# X-A4U-RGB.net
KiCad netlist of a schematic drawn in EAGLE
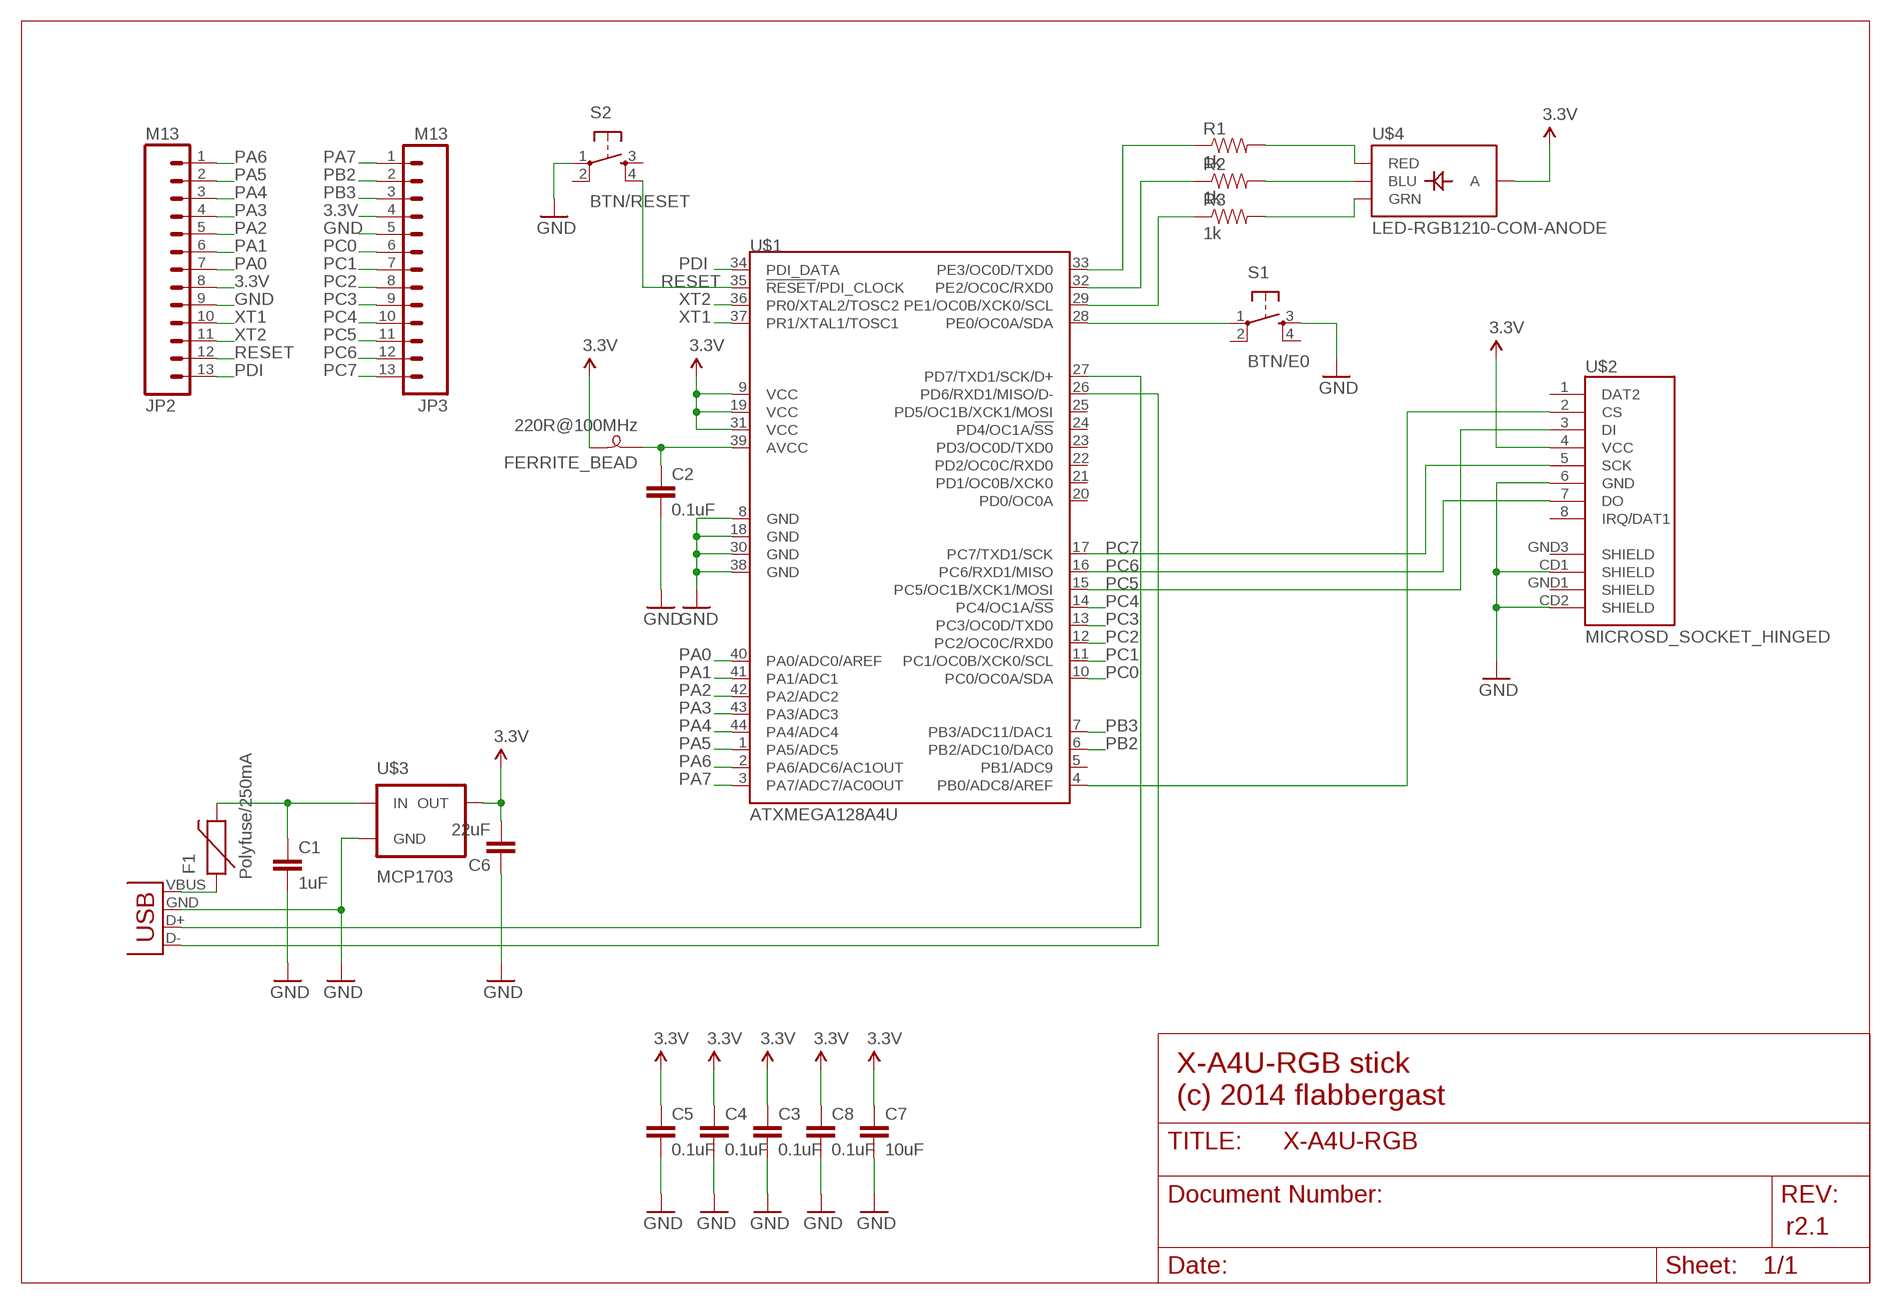
[diagram p0: schematic, sheet 1]

(export (version "E")
  (design (tool "Eeschema 10.0.6"))
  (components
    (comp (ref "C1")
      (value "1uF")
      (footprint "eagle-import:0805")
      (libsource (lib "eagle-import") (part "CAPACITOR0805"))
    )
    (comp (ref "C2")
      (value "0.1uF")
      (footprint "eagle-import:0805")
      (libsource (lib "eagle-import") (part "CAPACITOR0805"))
    )
    (comp (ref "C3")
      (value "0.1uF")
      (footprint "eagle-import:0805")
      (libsource (lib "eagle-import") (part "CAPACITOR0805"))
    )
    (comp (ref "C4")
      (value "0.1uF")
      (footprint "eagle-import:0805")
      (libsource (lib "eagle-import") (part "CAPACITOR0805"))
    )
    (comp (ref "C5")
      (value "0.1uF")
      (footprint "eagle-import:0805")
      (libsource (lib "eagle-import") (part "CAPACITOR0805"))
    )
    (comp (ref "C6")
      (value "22uF")
      (footprint "eagle-import:1206")
      (libsource (lib "eagle-import") (part "CAP1206"))
    )
    (comp (ref "C7")
      (value "10uF")
      (footprint "eagle-import:1206")
      (libsource (lib "eagle-import") (part "CAPACITOR1206"))
    )
    (comp (ref "C8")
      (value "0.1uF")
      (footprint "eagle-import:1206")
      (libsource (lib "eagle-import") (part "CAPACITOR1206"))
    )
    (comp (ref "F1")
      (value "Polyfuse/250mA")
      (footprint "eagle-import:PTC-1206-WIDE")
      (libsource (lib "eagle-import") (part "PTCSMD-W"))
    )
    (comp (ref "FERRITE_BEAD")
      (value "220R@100MHz")
      (footprint "eagle-import:0805")
      (libsource (lib "eagle-import") (part "FERRITE-BEAD0805"))
    )
    (comp (ref "JP1")
      (value "USB-A-H")
      (footprint "eagle-import:USB-A-H")
      (libsource (lib "eagle-import") (part "USB-A-H"))
    )
    (comp (ref "JP2")
      (value "M13")
      (footprint "eagle-import:1X13")
      (libsource (lib "eagle-import") (part "M13"))
    )
    (comp (ref "JP3")
      (value "M13")
      (footprint "eagle-import:1X13")
      (libsource (lib "eagle-import") (part "M13"))
    )
    (comp (ref "R1")
      (value "1k")
      (footprint "eagle-import:0805")
      (libsource (lib "eagle-import") (part "RESISTOR0805"))
    )
    (comp (ref "R2")
      (value "1k")
      (footprint "eagle-import:0805")
      (libsource (lib "eagle-import") (part "RESISTOR0805"))
    )
    (comp (ref "R3")
      (value "1k")
      (footprint "eagle-import:0805")
      (libsource (lib "eagle-import") (part "RESISTOR0805"))
    )
    (comp (ref "S1")
      (value "BTN/E0")
      (footprint "eagle-import:TACTILE-SWITCH-SMD")
      (libsource (lib "eagle-import") (part "TAC_SWITCHSMD"))
    )
    (comp (ref "S2")
      (value "BTN/RESET")
      (footprint "eagle-import:TACTILE-SWITCH-SMD")
      (libsource (lib "eagle-import") (part "TAC_SWITCHSMD"))
    )
    (comp (ref "U$1")
      (value "ATXMEGA128A4U")
      (footprint "eagle-import:TQFP-44")
      (libsource (lib "eagle-import") (part "ATXMEGA128A4U"))
    )
    (comp (ref "U$2")
      (value "MICROSD_SOCKET_HINGED")
      (footprint "eagle-import:MICROSD_SOCKET_SLIDE")
      (libsource (lib "eagle-import") (part "MICROSD_SOCKET_SLIDE"))
    )
    (comp (ref "U$3")
      (value "MCP1703")
      (footprint "eagle-import:SOT-89")
      (libsource (lib "eagle-import") (part "MCP1703"))
    )
    (comp (ref "U$4")
      (value "LED-RGB1210-COM-ANODE")
      (footprint "eagle-import:LED-RGB-1210")
      (libsource (lib "eagle-import") (part "LED-RGB1210-COM-ANODE"))
    )
  )
  (nets
    (net (code "1") (name "/PA0") (class "Default")
      (node (ref "JP2") (pin "7") (pinfunction "7_7") (pintype "passive"))
      (node (ref "U$1") (pin "40") (pinfunction "PA0/ADC0/AREF_40") (pintype "bidirectional"))
    )
    (net (code "2") (name "/PA1") (class "Default")
      (node (ref "JP2") (pin "6") (pinfunction "6_6") (pintype "passive"))
      (node (ref "U$1") (pin "41") (pinfunction "PA1/ADC1_41") (pintype "bidirectional"))
    )
    (net (code "3") (name "/PA2") (class "Default")
      (node (ref "JP2") (pin "5") (pinfunction "5_5") (pintype "passive"))
      (node (ref "U$1") (pin "42") (pinfunction "PA2/ADC2_42") (pintype "bidirectional"))
    )
    (net (code "4") (name "/PA3") (class "Default")
      (node (ref "JP2") (pin "4") (pinfunction "4_4") (pintype "passive"))
      (node (ref "U$1") (pin "43") (pinfunction "PA3/ADC3_43") (pintype "bidirectional"))
    )
    (net (code "5") (name "/PA4") (class "Default")
      (node (ref "JP2") (pin "3") (pinfunction "3_3") (pintype "passive"))
      (node (ref "U$1") (pin "44") (pinfunction "PA4/ADC4_44") (pintype "bidirectional"))
    )
    (net (code "6") (name "/PA5") (class "Default")
      (node (ref "JP2") (pin "2") (pinfunction "2_2") (pintype "passive"))
      (node (ref "U$1") (pin "1") (pinfunction "PA5/ADC5_1") (pintype "bidirectional"))
    )
    (net (code "7") (name "/PA6") (class "Default")
      (node (ref "JP2") (pin "1") (pinfunction "1_1") (pintype "passive"))
      (node (ref "U$1") (pin "2") (pinfunction "PA6/ADC6/AC1OUT_2") (pintype "bidirectional"))
    )
    (net (code "8") (name "/PA7") (class "Default")
      (node (ref "JP3") (pin "1") (pinfunction "1_1") (pintype "passive"))
      (node (ref "U$1") (pin "3") (pinfunction "PA7/ADC7/AC0OUT_3") (pintype "bidirectional"))
    )
    (net (code "9") (name "/PB2") (class "Default")
      (node (ref "JP3") (pin "2") (pinfunction "2_2") (pintype "passive"))
      (node (ref "U$1") (pin "6") (pinfunction "PB2/ADC10/DAC0_6") (pintype "bidirectional"))
    )
    (net (code "10") (name "/PB3") (class "Default")
      (node (ref "JP3") (pin "3") (pinfunction "3_3") (pintype "passive"))
      (node (ref "U$1") (pin "7") (pinfunction "PB3/ADC11/DAC1_7") (pintype "bidirectional"))
    )
    (net (code "11") (name "/PC0") (class "Default")
      (node (ref "JP3") (pin "6") (pinfunction "6_6") (pintype "passive"))
      (node (ref "U$1") (pin "10") (pinfunction "PC0/OC0A/SDA_10") (pintype "bidirectional"))
    )
    (net (code "12") (name "/PC1") (class "Default")
      (node (ref "JP3") (pin "7") (pinfunction "7_7") (pintype "passive"))
      (node (ref "U$1") (pin "11") (pinfunction "PC1/OC0B/XCK0/SCL_11") (pintype "bidirectional"))
    )
    (net (code "13") (name "/PC2") (class "Default")
      (node (ref "JP3") (pin "8") (pinfunction "8_8") (pintype "passive"))
      (node (ref "U$1") (pin "12") (pinfunction "PC2/OC0C/RXD0_12") (pintype "bidirectional"))
    )
    (net (code "14") (name "/PC3") (class "Default")
      (node (ref "JP3") (pin "9") (pinfunction "9_9") (pintype "passive"))
      (node (ref "U$1") (pin "13") (pinfunction "PC3/OC0D/TXD0_13") (pintype "bidirectional"))
    )
    (net (code "15") (name "/PC4") (class "Default")
      (node (ref "JP3") (pin "10") (pinfunction "10_10") (pintype "passive"))
      (node (ref "U$1") (pin "14") (pinfunction "PC4/OC1A/~{SS}_14") (pintype "bidirectional"))
    )
    (net (code "16") (name "/PC5") (class "Default")
      (node (ref "JP3") (pin "11") (pinfunction "11_11") (pintype "passive"))
      (node (ref "U$1") (pin "15") (pinfunction "PC5/OC1B/XCK1/MOSI_15") (pintype "bidirectional"))
      (node (ref "U$2") (pin "3") (pinfunction "DI_3") (pintype "bidirectional"))
    )
    (net (code "17") (name "/PC6") (class "Default")
      (node (ref "JP3") (pin "12") (pinfunction "12_12") (pintype "passive"))
      (node (ref "U$1") (pin "16") (pinfunction "PC6/RXD1/MISO_16") (pintype "bidirectional"))
      (node (ref "U$2") (pin "7") (pinfunction "DO_7") (pintype "bidirectional"))
    )
    (net (code "18") (name "/PC7") (class "Default")
      (node (ref "JP3") (pin "13") (pinfunction "13_13") (pintype "passive"))
      (node (ref "U$1") (pin "17") (pinfunction "PC7/TXD1/SCK_17") (pintype "bidirectional"))
      (node (ref "U$2") (pin "5") (pinfunction "SCK_5") (pintype "bidirectional"))
    )
    (net (code "19") (name "/PDI") (class "Default")
      (node (ref "JP2") (pin "13") (pinfunction "13_13") (pintype "passive"))
      (node (ref "U$1") (pin "34") (pinfunction "PDI_DATA_34") (pintype "bidirectional"))
    )
    (net (code "20") (name "/RESET") (class "Default")
      (node (ref "JP2") (pin "12") (pinfunction "12_12") (pintype "passive"))
      (node (ref "S2") (pin "4") (pinfunction "4_4") (pintype "passive"))
      (node (ref "U$1") (pin "35") (pinfunction "~{RESET}/PDI_CLOCK_35") (pintype "bidirectional"))
    )
    (net (code "21") (name "/XT1") (class "Default")
      (node (ref "JP2") (pin "10") (pinfunction "10_10") (pintype "passive"))
      (node (ref "U$1") (pin "37") (pinfunction "PR1/XTAL1/TOSC1_37") (pintype "bidirectional"))
    )
    (net (code "22") (name "/XT2") (class "Default")
      (node (ref "JP2") (pin "11") (pinfunction "11_11") (pintype "passive"))
      (node (ref "U$1") (pin "36") (pinfunction "PR0/XTAL2/TOSC2_36") (pintype "bidirectional"))
    )
    (net (code "23") (name "3.3V") (class "Default")
      (node (ref "C3") (pin "1") (pinfunction "1_1") (pintype "passive"))
      (node (ref "C4") (pin "1") (pinfunction "1_1") (pintype "passive"))
      (node (ref "C5") (pin "1") (pinfunction "1_1") (pintype "passive"))
      (node (ref "C6") (pin "2") (pinfunction "2_2") (pintype "passive"))
      (node (ref "C7") (pin "1") (pinfunction "1_1") (pintype "passive"))
      (node (ref "C8") (pin "1") (pinfunction "1_1") (pintype "passive"))
      (node (ref "FERRITE_BEAD") (pin "2") (pinfunction "2_2") (pintype "passive"))
      (node (ref "JP2") (pin "8") (pinfunction "8_8") (pintype "passive"))
      (node (ref "JP3") (pin "4") (pinfunction "4_4") (pintype "passive"))
      (node (ref "U$1") (pin "19") (pinfunction "VCC_19") (pintype "bidirectional"))
      (node (ref "U$1") (pin "31") (pinfunction "VCC_31") (pintype "bidirectional"))
      (node (ref "U$1") (pin "9") (pinfunction "VCC_9") (pintype "bidirectional"))
      (node (ref "U$2") (pin "4") (pinfunction "VCC_4") (pintype "bidirectional"))
      (node (ref "U$3") (pin "3") (pinfunction "OUT_3") (pintype "passive"))
      (node (ref "U$4") (pin "A") (pinfunction "A_A") (pintype "bidirectional"))
    )
    (net (code "24") (name "GND") (class "Default")
      (node (ref "C1") (pin "2") (pinfunction "2_2") (pintype "passive"))
      (node (ref "C2") (pin "2") (pinfunction "2_2") (pintype "passive"))
      (node (ref "C3") (pin "2") (pinfunction "2_2") (pintype "passive"))
      (node (ref "C4") (pin "2") (pinfunction "2_2") (pintype "passive"))
      (node (ref "C5") (pin "2") (pinfunction "2_2") (pintype "passive"))
      (node (ref "C6") (pin "1") (pinfunction "1_1") (pintype "passive"))
      (node (ref "C7") (pin "2") (pinfunction "2_2") (pintype "passive"))
      (node (ref "C8") (pin "2") (pinfunction "2_2") (pintype "passive"))
      (node (ref "JP1") (pin "GND") (pinfunction "VBUS_GND") (pintype "bidirectional"))
      (node (ref "JP2") (pin "9") (pinfunction "9_9") (pintype "passive"))
      (node (ref "JP3") (pin "5") (pinfunction "5_5") (pintype "passive"))
      (node (ref "S1") (pin "3") (pinfunction "3_3") (pintype "passive"))
      (node (ref "S2") (pin "1") (pinfunction "1_1") (pintype "passive"))
      (node (ref "U$1") (pin "18") (pinfunction "GND_18") (pintype "bidirectional"))
      (node (ref "U$1") (pin "30") (pinfunction "GND_30") (pintype "bidirectional"))
      (node (ref "U$1") (pin "38") (pinfunction "GND_38") (pintype "bidirectional"))
      (node (ref "U$1") (pin "8") (pinfunction "GND_8") (pintype "bidirectional"))
      (node (ref "U$2") (pin "6") (pinfunction "GND_6") (pintype "bidirectional"))
      (node (ref "U$2") (pin "CD1") (pinfunction "SHIELD_CD1") (pintype "bidirectional"))
      (node (ref "U$2") (pin "CD2") (pinfunction "SHIELD_CD2") (pintype "bidirectional"))
      (node (ref "U$3") (pin "1") (pinfunction "GND_1") (pintype "input"))
    )
    (net (code "25") (name "Net-(C1-Pad1)") (class "Default")
      (node (ref "C1") (pin "1") (pinfunction "1_1") (pintype "passive"))
      (node (ref "F1") (pin "2") (pinfunction "2_2") (pintype "bidirectional"))
      (node (ref "U$3") (pin "2") (pinfunction "IN_2") (pintype "input"))
      (node (ref "U$3") (pin "4") (pinfunction "IN_4") (pintype "input"))
    )
    (net (code "26") (name "Net-(JP1-D+)") (class "Default")
      (node (ref "JP1") (pin "D-") (pinfunction "D+_D-") (pintype "bidirectional"))
      (node (ref "U$1") (pin "26") (pinfunction "PD6/RXD1/MISO/D-_26") (pintype "bidirectional"))
    )
    (net (code "27") (name "Net-(JP1-D-)") (class "Default")
      (node (ref "JP1") (pin "D+") (pinfunction "D-_D+") (pintype "bidirectional"))
      (node (ref "U$1") (pin "27") (pinfunction "PD7/TXD1/SCK/D+_27") (pintype "bidirectional"))
    )
    (net (code "28") (name "Net-(JP1-GND)") (class "Default")
      (node (ref "F1") (pin "1") (pinfunction "1_1") (pintype "bidirectional"))
      (node (ref "JP1") (pin "VBUS") (pinfunction "GND_VBUS") (pintype "bidirectional"))
    )
    (net (code "29") (name "Net-(U$1-AVCC)") (class "Default")
      (node (ref "C2") (pin "1") (pinfunction "1_1") (pintype "passive"))
      (node (ref "FERRITE_BEAD") (pin "1") (pinfunction "1_1") (pintype "passive"))
      (node (ref "U$1") (pin "39") (pinfunction "AVCC_39") (pintype "bidirectional"))
    )
    (net (code "30") (name "Net-(U$1-PB0{slash}ADC8{slash}AREF)") (class "Default")
      (node (ref "U$1") (pin "4") (pinfunction "PB0/ADC8/AREF_4") (pintype "bidirectional"))
      (node (ref "U$2") (pin "2") (pinfunction "CS_2") (pintype "bidirectional"))
    )
    (net (code "31") (name "Net-(U$1-PE0{slash}OC0A{slash}SDA)") (class "Default")
      (node (ref "S1") (pin "1") (pinfunction "1_1") (pintype "passive"))
      (node (ref "U$1") (pin "28") (pinfunction "PE0/OC0A/SDA_28") (pintype "bidirectional"))
    )
    (net (code "32") (name "Net-(U$1-PE1{slash}OC0B{slash}XCK0{slash}SCL)") (class "Default")
      (node (ref "R3") (pin "1") (pinfunction "1_1") (pintype "passive"))
      (node (ref "U$1") (pin "29") (pinfunction "PE1/OC0B/XCK0/SCL_29") (pintype "bidirectional"))
    )
    (net (code "33") (name "Net-(U$1-PE2{slash}OC0C{slash}RXD0)") (class "Default")
      (node (ref "R2") (pin "1") (pinfunction "1_1") (pintype "passive"))
      (node (ref "U$1") (pin "32") (pinfunction "PE2/OC0C/RXD0_32") (pintype "bidirectional"))
    )
    (net (code "34") (name "Net-(U$1-PE3{slash}OC0D{slash}TXD0)") (class "Default")
      (node (ref "R1") (pin "1") (pinfunction "1_1") (pintype "passive"))
      (node (ref "U$1") (pin "33") (pinfunction "PE3/OC0D/TXD0_33") (pintype "bidirectional"))
    )
    (net (code "35") (name "Net-(U$4-BLU)") (class "Default")
      (node (ref "R2") (pin "2") (pinfunction "2_2") (pintype "passive"))
      (node (ref "U$4") (pin "B") (pinfunction "BLU_B") (pintype "bidirectional"))
    )
    (net (code "36") (name "Net-(U$4-GRN)") (class "Default")
      (node (ref "R3") (pin "2") (pinfunction "2_2") (pintype "passive"))
      (node (ref "U$4") (pin "G") (pinfunction "GRN_G") (pintype "bidirectional"))
    )
    (net (code "37") (name "Net-(U$4-RED)") (class "Default")
      (node (ref "R1") (pin "2") (pinfunction "2_2") (pintype "passive"))
      (node (ref "U$4") (pin "R") (pinfunction "RED_R") (pintype "bidirectional"))
    )
    (net (code "38") (name "unconnected-(S1-Pad2)") (class "Default")
      (node (ref "S1") (pin "2") (pinfunction "2_2") (pintype "passive"))
    )
    (net (code "39") (name "unconnected-(S1-Pad4)") (class "Default")
      (node (ref "S1") (pin "4") (pinfunction "4_4") (pintype "passive"))
    )
    (net (code "40") (name "unconnected-(S2-Pad2)") (class "Default")
      (node (ref "S2") (pin "2") (pinfunction "2_2") (pintype "passive"))
    )
    (net (code "41") (name "unconnected-(S2-Pad3)") (class "Default")
      (node (ref "S2") (pin "3") (pinfunction "3_3") (pintype "passive"))
    )
    (net (code "42") (name "unconnected-(U$1-PB1{slash}ADC9-Pad5)") (class "Default")
      (node (ref "U$1") (pin "5") (pinfunction "PB1/ADC9_5") (pintype "bidirectional"))
    )
    (net (code "43") (name "unconnected-(U$1-PD0{slash}OC0A-Pad20)") (class "Default")
      (node (ref "U$1") (pin "20") (pinfunction "PD0/OC0A_20") (pintype "bidirectional"))
    )
    (net (code "44") (name "unconnected-(U$1-PD1{slash}OC0B{slash}XCK0-Pad21)") (class "Default")
      (node (ref "U$1") (pin "21") (pinfunction "PD1/OC0B/XCK0_21") (pintype "bidirectional"))
    )
    (net (code "45") (name "unconnected-(U$1-PD2{slash}OC0C{slash}RXD0-Pad22)") (class "Default")
      (node (ref "U$1") (pin "22") (pinfunction "PD2/OC0C/RXD0_22") (pintype "bidirectional"))
    )
    (net (code "46") (name "unconnected-(U$1-PD3{slash}OC0D{slash}TXD0-Pad23)") (class "Default")
      (node (ref "U$1") (pin "23") (pinfunction "PD3/OC0D/TXD0_23") (pintype "bidirectional"))
    )
    (net (code "47") (name "unconnected-(U$1-PD4{slash}OC1A{slash}~{SS}-Pad24)") (class "Default")
      (node (ref "U$1") (pin "24") (pinfunction "PD4/OC1A/~{SS}_24") (pintype "bidirectional"))
    )
    (net (code "48") (name "unconnected-(U$1-PD5{slash}OC1B{slash}XCK1{slash}MOSI-Pad25)") (class "Default")
      (node (ref "U$1") (pin "25") (pinfunction "PD5/OC1B/XCK1/MOSI_25") (pintype "bidirectional"))
    )
    (net (code "49") (name "unconnected-(U$2-DAT2-Pad1)") (class "Default")
      (node (ref "U$2") (pin "1") (pinfunction "DAT2_1") (pintype "bidirectional"))
    )
    (net (code "50") (name "unconnected-(U$2-IRQ{slash}DAT1-Pad8)") (class "Default")
      (node (ref "U$2") (pin "8") (pinfunction "IRQ/DAT1_8") (pintype "bidirectional"))
    )
    (net (code "51") (name "unconnected-(U$2-SHIELD-PadGND1)") (class "Default")
      (node (ref "U$2") (pin "GND1") (pinfunction "SHIELD_GND1") (pintype "bidirectional"))
    )
    (net (code "52") (name "unconnected-(U$2-SHIELD-PadGND3)") (class "Default")
      (node (ref "U$2") (pin "GND3") (pinfunction "SHIELD_GND3") (pintype "bidirectional"))
    )
  )
)
